# Emoji_Board_v3.net
KiCad netlist of a schematic drawn in EAGLE
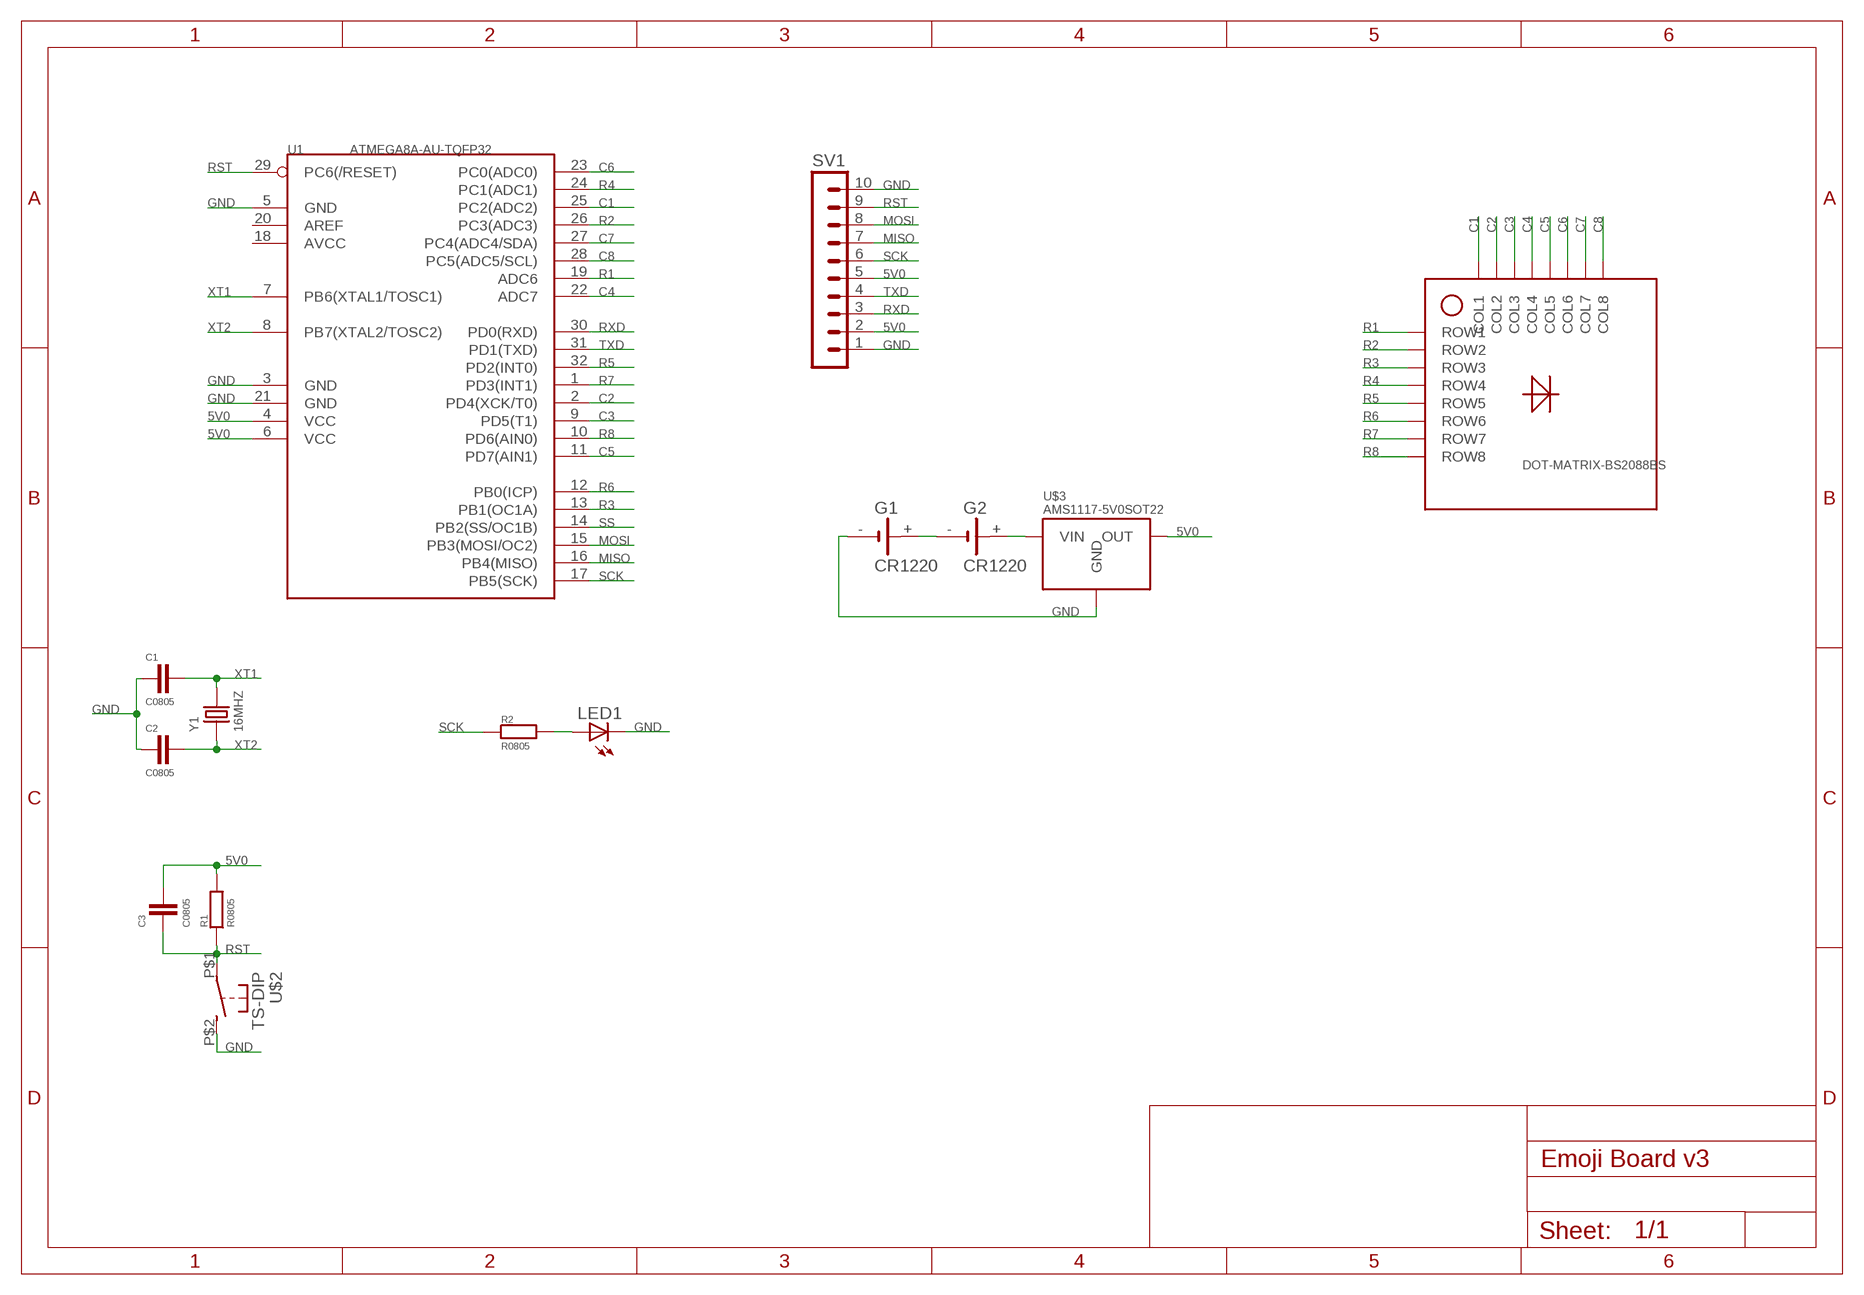
[diagram p0: schematic, sheet 1]

(export (version "E")
  (design (tool "Eeschema 10.0.6"))
  (components
    (comp (ref "C1")
      (value "C0805")
      (footprint "eagle-import:C0805")
      (libsource (lib "eagle-import") (part "C0805"))
    )
    (comp (ref "C2")
      (value "C0805")
      (footprint "eagle-import:C0805")
      (libsource (lib "eagle-import") (part "C0805"))
    )
    (comp (ref "C3")
      (value "C0805")
      (footprint "eagle-import:C0805")
      (libsource (lib "eagle-import") (part "C0805"))
    )
    (comp (ref "G1")
      (value "CR1220")
      (footprint "eagle-import:CR1220")
      (libsource (lib "eagle-import") (part "CR1220"))
    )
    (comp (ref "G2")
      (value "CR1220")
      (footprint "eagle-import:CR1220")
      (libsource (lib "eagle-import") (part "CR1220"))
    )
    (comp (ref "LED1")
      (value "LEDCHIPLED_0805")
      (footprint "eagle-import:LED0805")
      (libsource (lib "eagle-import") (part "LEDCHIPLED_0805"))
    )
    (comp (ref "R1")
      (value "R0805")
      (footprint "eagle-import:R0805")
      (libsource (lib "eagle-import") (part "R0805"))
    )
    (comp (ref "R2")
      (value "R0805")
      (footprint "eagle-import:R0805")
      (libsource (lib "eagle-import") (part "R0805"))
    )
    (comp (ref "SV1")
      (value "MA10-1W")
      (footprint "eagle-import:MA10-1W")
      (libsource (lib "eagle-import") (part "MA10-1W"))
    )
    (comp (ref "U$1")
      (value "DOT-MATRIX-BS2088BS")
      (footprint "eagle-import:2088BS")
      (libsource (lib "eagle-import") (part "DOT-MATRIX-BS2088BS"))
    )
    (comp (ref "U$2")
      (value "TS-DIP")
      (footprint "eagle-import:TS-DIP")
      (libsource (lib "eagle-import") (part "TS-DIP"))
    )
    (comp (ref "U$3")
      (value "AMS1117-5V0SOT22")
      (footprint "eagle-import:SOT223")
      (libsource (lib "eagle-import") (part "AMS1117-5V0SOT22"))
    )
    (comp (ref "U1")
      (value "ATMEGA8A-AU-TQFP32")
      (footprint "eagle-import:TQFP32")
      (fields (field (name "MPN") "ATMEGA8A-AU"))
      (libsource (lib "eagle-import") (part "ATMEGA8A-AU"))
    )
    (comp (ref "Y1")
      (value "16MHZ")
      (footprint "eagle-import:HC49US")
      (fields (field (name "MPN") "HC-49US    16.000MHz"))
      (libsource (lib "eagle-import") (part "DIP-CRYSTAL-16MHZ-18PF-30PPM-40R(HC49US)"))
    )
  )
  (nets
    (net (code "1") (name "/5V0") (class "Default")
      (node (ref "C3") (pin "1") (pinfunction "1_1") (pintype "bidirectional"))
      (node (ref "R1") (pin "2") (pinfunction "2_2") (pintype "bidirectional"))
      (node (ref "SV1") (pin "2") (pinfunction "2_2") (pintype "passive"))
      (node (ref "SV1") (pin "5") (pinfunction "5_5") (pintype "passive"))
      (node (ref "U$3") (pin "OUT") (pinfunction "OUT_OUT") (pintype "bidirectional"))
      (node (ref "U1") (pin "4") (pinfunction "VCC_4") (pintype "bidirectional"))
      (node (ref "U1") (pin "6") (pinfunction "VCC_6") (pintype "bidirectional"))
    )
    (net (code "2") (name "/C1") (class "Default")
      (node (ref "U$1") (pin "COL1") (pinfunction "COL1_COL1") (pintype "bidirectional"))
      (node (ref "U1") (pin "25") (pinfunction "PC2(ADC2)_25") (pintype "bidirectional"))
    )
    (net (code "3") (name "/C2") (class "Default")
      (node (ref "U$1") (pin "COL2") (pinfunction "COL2_COL2") (pintype "bidirectional"))
      (node (ref "U1") (pin "2") (pinfunction "PD4(XCK/T0)_2") (pintype "bidirectional"))
    )
    (net (code "4") (name "/C3") (class "Default")
      (node (ref "U$1") (pin "COL3") (pinfunction "COL3_COL3") (pintype "bidirectional"))
      (node (ref "U1") (pin "9") (pinfunction "PD5(T1)_9") (pintype "bidirectional"))
    )
    (net (code "5") (name "/C4") (class "Default")
      (node (ref "U$1") (pin "COL4") (pinfunction "COL4_COL4") (pintype "bidirectional"))
      (node (ref "U1") (pin "22") (pinfunction "ADC7_22") (pintype "bidirectional"))
    )
    (net (code "6") (name "/C5") (class "Default")
      (node (ref "U$1") (pin "COL5") (pinfunction "COL5_COL5") (pintype "bidirectional"))
      (node (ref "U1") (pin "11") (pinfunction "PD7(AIN1)_11") (pintype "bidirectional"))
    )
    (net (code "7") (name "/C6") (class "Default")
      (node (ref "U$1") (pin "COL6") (pinfunction "COL6_COL6") (pintype "bidirectional"))
      (node (ref "U1") (pin "23") (pinfunction "PC0(ADC0)_23") (pintype "bidirectional"))
    )
    (net (code "8") (name "/C7") (class "Default")
      (node (ref "U$1") (pin "COL7") (pinfunction "COL7_COL7") (pintype "bidirectional"))
      (node (ref "U1") (pin "27") (pinfunction "PC4(ADC4/SDA)_27") (pintype "bidirectional"))
    )
    (net (code "9") (name "/C8") (class "Default")
      (node (ref "U$1") (pin "COL8") (pinfunction "COL8_COL8") (pintype "bidirectional"))
      (node (ref "U1") (pin "28") (pinfunction "PC5(ADC5/SCL)_28") (pintype "bidirectional"))
    )
    (net (code "10") (name "/GND") (class "Default")
      (node (ref "C1") (pin "2") (pinfunction "2_2") (pintype "bidirectional"))
      (node (ref "C2") (pin "2") (pinfunction "2_2") (pintype "bidirectional"))
      (node (ref "G1") (pin "-") (pinfunction "-_-") (pintype "passive"))
      (node (ref "LED1") (pin "C") (pinfunction "C_C") (pintype "passive"))
      (node (ref "SV1") (pin "1") (pinfunction "1_1") (pintype "passive"))
      (node (ref "SV1") (pin "10") (pinfunction "10_10") (pintype "passive"))
      (node (ref "U$2") (pin "P$2") (pinfunction "S_P$2") (pintype "passive"))
      (node (ref "U$3") (pin "GND") (pinfunction "GND_GND") (pintype "bidirectional"))
      (node (ref "U1") (pin "21") (pinfunction "GND_21") (pintype "bidirectional"))
      (node (ref "U1") (pin "3") (pinfunction "GND_3") (pintype "bidirectional"))
      (node (ref "U1") (pin "5") (pinfunction "GND_5") (pintype "bidirectional"))
    )
    (net (code "11") (name "/MISO") (class "Default")
      (node (ref "SV1") (pin "7") (pinfunction "7_7") (pintype "passive"))
      (node (ref "U1") (pin "16") (pinfunction "PB4(MISO)_16") (pintype "bidirectional"))
    )
    (net (code "12") (name "/MOSI") (class "Default")
      (node (ref "SV1") (pin "8") (pinfunction "8_8") (pintype "passive"))
      (node (ref "U1") (pin "15") (pinfunction "PB3(MOSI/OC2)_15") (pintype "bidirectional"))
    )
    (net (code "13") (name "/R1") (class "Default")
      (node (ref "U$1") (pin "ROW1") (pinfunction "ROW1_ROW1") (pintype "bidirectional"))
      (node (ref "U1") (pin "19") (pinfunction "ADC6_19") (pintype "bidirectional"))
    )
    (net (code "14") (name "/R2") (class "Default")
      (node (ref "U$1") (pin "ROW2") (pinfunction "ROW2_ROW2") (pintype "bidirectional"))
      (node (ref "U1") (pin "26") (pinfunction "PC3(ADC3)_26") (pintype "bidirectional"))
    )
    (net (code "15") (name "/R3") (class "Default")
      (node (ref "U$1") (pin "ROW3") (pinfunction "ROW3_ROW3") (pintype "bidirectional"))
      (node (ref "U1") (pin "13") (pinfunction "PB1(OC1A)_13") (pintype "bidirectional"))
    )
    (net (code "16") (name "/R4") (class "Default")
      (node (ref "U$1") (pin "ROW4") (pinfunction "ROW4_ROW4") (pintype "bidirectional"))
      (node (ref "U1") (pin "24") (pinfunction "PC1(ADC1)_24") (pintype "bidirectional"))
    )
    (net (code "17") (name "/R5") (class "Default")
      (node (ref "U$1") (pin "ROW5") (pinfunction "ROW5_ROW5") (pintype "bidirectional"))
      (node (ref "U1") (pin "32") (pinfunction "PD2(INT0)_32") (pintype "bidirectional"))
    )
    (net (code "18") (name "/R6") (class "Default")
      (node (ref "U$1") (pin "ROW6") (pinfunction "ROW6_ROW6") (pintype "bidirectional"))
      (node (ref "U1") (pin "12") (pinfunction "PB0(ICP)_12") (pintype "bidirectional"))
    )
    (net (code "19") (name "/R7") (class "Default")
      (node (ref "U$1") (pin "ROW7") (pinfunction "ROW7_ROW7") (pintype "bidirectional"))
      (node (ref "U1") (pin "1") (pinfunction "PD3(INT1)_1") (pintype "bidirectional"))
    )
    (net (code "20") (name "/R8") (class "Default")
      (node (ref "U$1") (pin "ROW8") (pinfunction "ROW8_ROW8") (pintype "bidirectional"))
      (node (ref "U1") (pin "10") (pinfunction "PD6(AIN0)_10") (pintype "bidirectional"))
    )
    (net (code "21") (name "/RST") (class "Default")
      (node (ref "C3") (pin "2") (pinfunction "2_2") (pintype "bidirectional"))
      (node (ref "R1") (pin "1") (pinfunction "1_1") (pintype "bidirectional"))
      (node (ref "SV1") (pin "9") (pinfunction "9_9") (pintype "passive"))
      (node (ref "U$2") (pin "P$1") (pinfunction "P_P$1") (pintype "passive"))
      (node (ref "U1") (pin "29") (pinfunction "PC6(/RESET)_29") (pintype "bidirectional"))
    )
    (net (code "22") (name "/RXD") (class "Default")
      (node (ref "SV1") (pin "3") (pinfunction "3_3") (pintype "passive"))
      (node (ref "U1") (pin "30") (pinfunction "PD0(RXD)_30") (pintype "bidirectional"))
    )
    (net (code "23") (name "/SCK") (class "Default")
      (node (ref "R2") (pin "1") (pinfunction "1_1") (pintype "bidirectional"))
      (node (ref "SV1") (pin "6") (pinfunction "6_6") (pintype "passive"))
      (node (ref "U1") (pin "17") (pinfunction "PB5(SCK)_17") (pintype "bidirectional"))
    )
    (net (code "24") (name "/SS") (class "Default")
      (node (ref "U1") (pin "14") (pinfunction "PB2(SS/OC1B)_14") (pintype "bidirectional"))
    )
    (net (code "25") (name "/TXD") (class "Default")
      (node (ref "SV1") (pin "4") (pinfunction "4_4") (pintype "passive"))
      (node (ref "U1") (pin "31") (pinfunction "PD1(TXD)_31") (pintype "bidirectional"))
    )
    (net (code "26") (name "/XT1") (class "Default")
      (node (ref "C1") (pin "1") (pinfunction "1_1") (pintype "bidirectional"))
      (node (ref "U1") (pin "7") (pinfunction "PB6(XTAL1/TOSC1)_7") (pintype "bidirectional"))
      (node (ref "Y1") (pin "2") (pinfunction "2_2") (pintype "passive"))
    )
    (net (code "27") (name "/XT2") (class "Default")
      (node (ref "C2") (pin "1") (pinfunction "1_1") (pintype "bidirectional"))
      (node (ref "U1") (pin "8") (pinfunction "PB7(XTAL2/TOSC2)_8") (pintype "bidirectional"))
      (node (ref "Y1") (pin "1") (pinfunction "1_1") (pintype "passive"))
    )
    (net (code "28") (name "Net-(G1-Pad+)") (class "Default")
      (node (ref "G1") (pin "+") (pinfunction "+_+") (pintype "passive"))
      (node (ref "G2") (pin "-") (pinfunction "-_-") (pintype "passive"))
    )
    (net (code "29") (name "Net-(G2-Pad+)") (class "Default")
      (node (ref "G2") (pin "+") (pinfunction "+_+") (pintype "passive"))
      (node (ref "U$3") (pin "VIN") (pinfunction "VIN_VIN") (pintype "bidirectional"))
    )
    (net (code "30") (name "Net-(LED1-PadA)") (class "Default")
      (node (ref "LED1") (pin "A") (pinfunction "A_A") (pintype "passive"))
      (node (ref "R2") (pin "2") (pinfunction "2_2") (pintype "bidirectional"))
    )
    (net (code "31") (name "unconnected-(U1-AREF-Pad20)") (class "Default")
      (node (ref "U1") (pin "20") (pinfunction "AREF_20") (pintype "bidirectional"))
    )
    (net (code "32") (name "unconnected-(U1-AVCC-Pad18)") (class "Default")
      (node (ref "U1") (pin "18") (pinfunction "AVCC_18") (pintype "bidirectional"))
    )
  )
)
